# max6_breakout_1575AT43A40.net
KiCad netlist of a schematic drawn in EAGLE
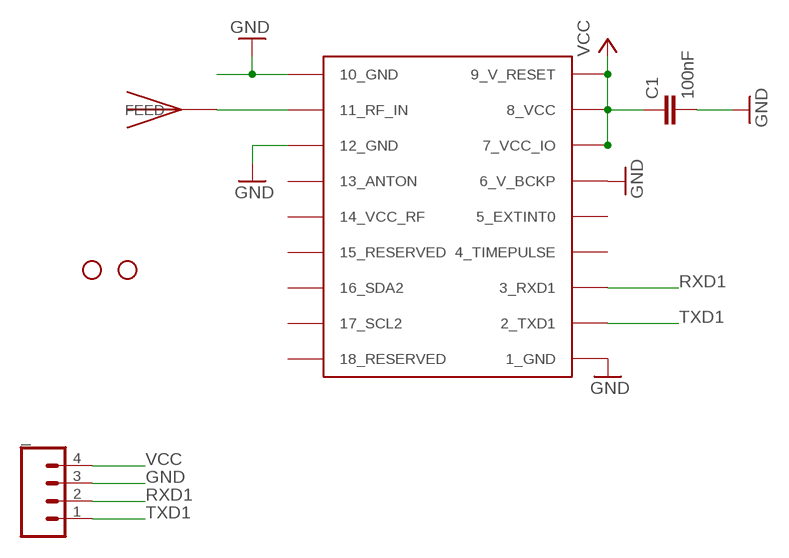
[diagram p0: schematic, sheet 1]

(export (version "E")
  (design (tool "Eeschema 10.0.6"))
  (components
    (comp (ref "C1")
      (value "100nF")
      (footprint "eagle-import:0603-CAP")
      (libsource (lib "eagle-import") (part "CAP0603-CAP"))
    )
    (comp (ref "JP1")
      (value "STAND-OFF")
      (footprint "eagle-import:STAND-OFF")
      (libsource (lib "eagle-import") (part "STAND-OFF"))
    )
    (comp (ref "JP2")
      (value "STAND-OFF")
      (footprint "eagle-import:STAND-OFF")
      (libsource (lib "eagle-import") (part "STAND-OFF"))
    )
    (comp (ref "U$1")
      (value "UBLOX_MAX-6")
      (footprint "eagle-import:UBLOX_MAX-6")
      (libsource (lib "eagle-import") (part "UBLOX_MAX-6"))
    )
    (comp (ref "U$2")
      (value "JTI_ANTENNA-1575AT43A40")
      (footprint "eagle-import:JTI_ANTENNA-1575AT43A40")
      (libsource (lib "eagle-import") (part "JTI_ANTENNA-1575AT43A40"))
    )
    (comp (ref "_")
      (value "M04PTH")
      (footprint "eagle-import:1X04")
      (libsource (lib "eagle-import") (part "M04PTH"))
    )
  )
  (nets
    (net (code "1") (name "/RXD1") (class "Default")
      (node (ref "U$1") (pin "3_RXD1") (pinfunction "3_RXD1_3_RXD1") (pintype "bidirectional"))
      (node (ref "_") (pin "2") (pinfunction "2_2") (pintype "passive"))
    )
    (net (code "2") (name "/TXD1") (class "Default")
      (node (ref "U$1") (pin "2_TXD1") (pinfunction "2_TXD1_2_TXD1") (pintype "bidirectional"))
      (node (ref "_") (pin "1") (pinfunction "1_1") (pintype "passive"))
    )
    (net (code "3") (name "GND") (class "Default")
      (node (ref "C1") (pin "2") (pinfunction "2_2") (pintype "passive"))
      (node (ref "U$1") (pin "10_GND") (pinfunction "10_GND_10_GND") (pintype "bidirectional"))
      (node (ref "U$1") (pin "12_GND") (pinfunction "12_GND_12_GND") (pintype "bidirectional"))
      (node (ref "U$1") (pin "1_GND") (pinfunction "1_GND_1_GND") (pintype "bidirectional"))
      (node (ref "U$1") (pin "6_V_BCKP") (pinfunction "6_V_BCKP_6_V_BCKP") (pintype "bidirectional"))
      (node (ref "_") (pin "3") (pinfunction "3_3") (pintype "passive"))
    )
    (net (code "4") (name "Net-(U$1-Pad11_RF_IN)") (class "Default")
      (node (ref "U$1") (pin "11_RF_IN") (pinfunction "11_RF_IN_11_RF_IN") (pintype "bidirectional"))
      (node (ref "U$2") (pin "FEED") (pinfunction "FEED_FEED") (pintype "bidirectional"))
    )
    (net (code "5") (name "VCC") (class "Default")
      (node (ref "C1") (pin "1") (pinfunction "1_1") (pintype "passive"))
      (node (ref "U$1") (pin "7_VCC_IO") (pinfunction "7_VCC_IO_7_VCC_IO") (pintype "bidirectional"))
      (node (ref "U$1") (pin "8_VCC") (pinfunction "8_VCC_8_VCC") (pintype "bidirectional"))
      (node (ref "U$1") (pin "9_V_RESET") (pinfunction "9_V_RESET_9_V_RESET") (pintype "bidirectional"))
      (node (ref "_") (pin "4") (pinfunction "4_4") (pintype "passive"))
    )
    (net (code "6") (name "unconnected-(U$1-Pad4_TIMEPULSE)") (class "Default")
      (node (ref "U$1") (pin "4_TIMEPULSE") (pinfunction "4_TIMEPULSE_4_TIMEPULSE") (pintype "bidirectional"))
    )
    (net (code "7") (name "unconnected-(U$1-Pad5_EXTINT0)") (class "Default")
      (node (ref "U$1") (pin "5_EXTINT0") (pinfunction "5_EXTINT0_5_EXTINT0") (pintype "bidirectional"))
    )
    (net (code "8") (name "unconnected-(U$1-Pad13_ANTON)") (class "Default")
      (node (ref "U$1") (pin "13_ANTON") (pinfunction "13_ANTON_13_ANTON") (pintype "bidirectional"))
    )
    (net (code "9") (name "unconnected-(U$1-Pad14_VCC_RF)") (class "Default")
      (node (ref "U$1") (pin "14_VCC_RF") (pinfunction "14_VCC_RF_14_VCC_RF") (pintype "bidirectional"))
    )
    (net (code "10") (name "unconnected-(U$1-Pad15_RESERVED)") (class "Default")
      (node (ref "U$1") (pin "15_RESERVED") (pinfunction "15_RESERVED_15_RESERVED") (pintype "bidirectional"))
    )
    (net (code "11") (name "unconnected-(U$1-Pad16_SDA2)") (class "Default")
      (node (ref "U$1") (pin "16_SDA2") (pinfunction "16_SDA2_16_SDA2") (pintype "bidirectional"))
    )
    (net (code "12") (name "unconnected-(U$1-Pad17_SCL2)") (class "Default")
      (node (ref "U$1") (pin "17_SCL2") (pinfunction "17_SCL2_17_SCL2") (pintype "bidirectional"))
    )
    (net (code "13") (name "unconnected-(U$1-Pad18_RESERVED)") (class "Default")
      (node (ref "U$1") (pin "18_RESERVED") (pinfunction "18_RESERVED_18_RESERVED") (pintype "bidirectional"))
    )
  )
)
